# cc2652p2-tcp.net
KiCad netlist of a schematic drawn in EAGLE
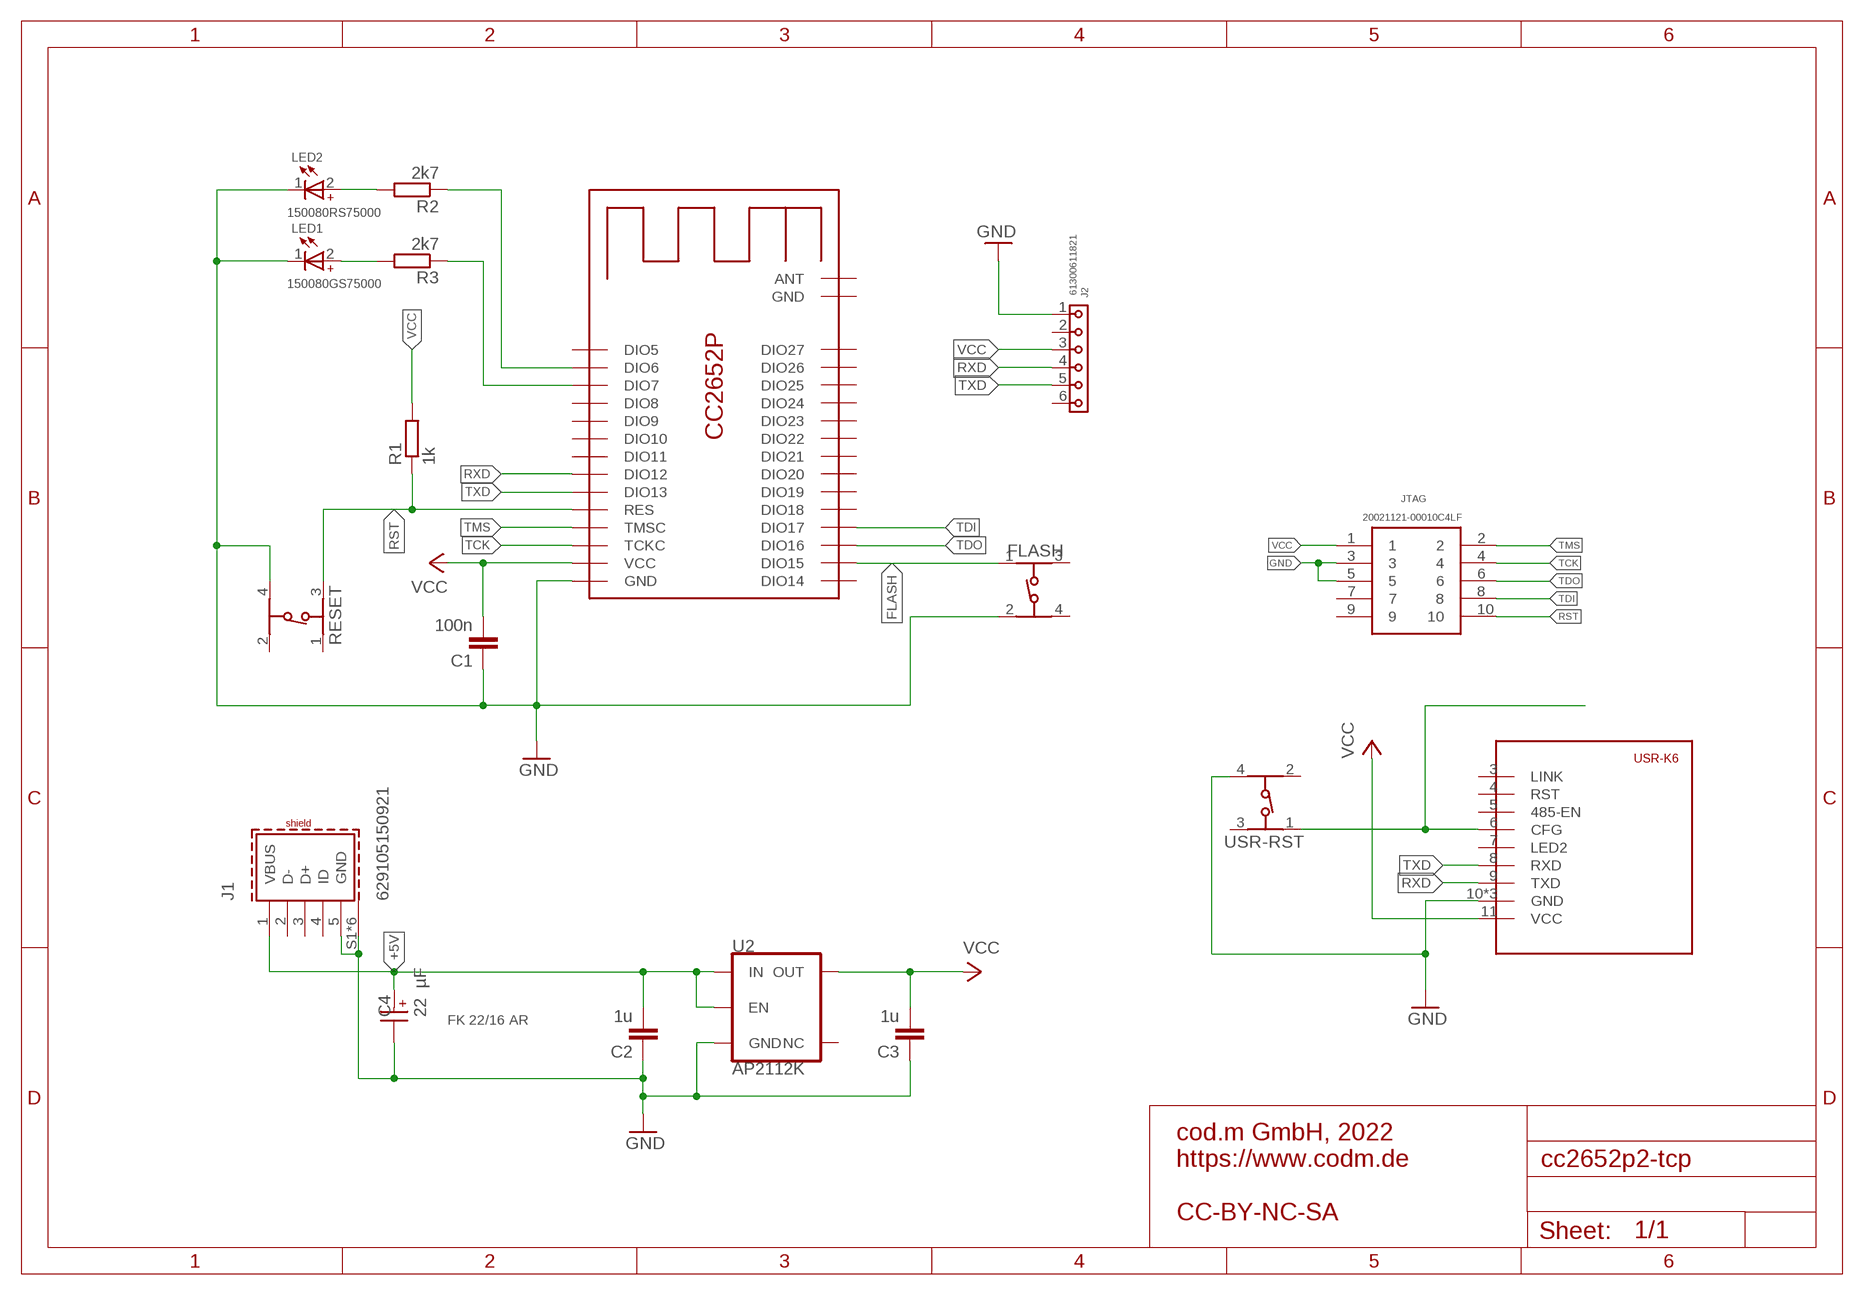
[diagram p0: schematic, sheet 1]

(export (version "E")
  (design (tool "Eeschema 10.0.6"))
  (components
    (comp (ref "C1")
      (value "100n")
      (footprint "eagle-import:C0805")
      (libsource (lib "eagle-import") (part "C-EUC0805"))
    )
    (comp (ref "C2")
      (value "1u")
      (footprint "eagle-import:C0805")
      (libsource (lib "eagle-import") (part "C-EUC0805"))
    )
    (comp (ref "C3")
      (value "1u")
      (footprint "eagle-import:C0805")
      (libsource (lib "eagle-import") (part "C-EUC0805"))
    )
    (comp (ref "C4")
      (value "22 µF")
      (footprint "eagle-import:WCAP-ASLL_5X5.5(DXL)")
      (libsource (lib "eagle-import") (part "WCAP-ASLL_5X5.5_865060342002"))
    )
    (comp (ref "FLASH")
      (value "434153017835")
      (footprint "eagle-import:434153017835")
      (libsource (lib "eagle-import") (part "434153017835"))
    )
    (comp (ref "J1")
      (value "629105150921")
      (footprint "eagle-import:629105150921")
      (libsource (lib "eagle-import") (part "629105150921"))
    )
    (comp (ref "J2")
      (value "61300611821")
      (footprint "eagle-import:61300611821")
      (libsource (lib "eagle-import") (part "6130XX11821_61300611821"))
    )
    (comp (ref "JTAG")
      (value "20021121-00010C4LF")
      (footprint "eagle-import:2002112100010C4LF")
      (fields (field (name "MOUSER_PART_NUMBER") "649-202112100010C4LF"))
      (libsource (lib "eagle-import") (part "20021121-00010C4LF"))
    )
    (comp (ref "LED1")
      (value "150080GS75000")
      (footprint "eagle-import:WL-SMCW_0805")
      (libsource (lib "eagle-import") (part "WL-SMCW_0805_150080GS75000"))
    )
    (comp (ref "LED2")
      (value "150080RS75000")
      (footprint "eagle-import:WL-SMCW_0805")
      (libsource (lib "eagle-import") (part "WL-SMCW_0805_150080RS75000"))
    )
    (comp (ref "R1")
      (value "1k")
      (footprint "eagle-import:R0805")
      (libsource (lib "eagle-import") (part "R-EU_R0805"))
    )
    (comp (ref "R2")
      (value "2k7")
      (footprint "eagle-import:R0805")
      (libsource (lib "eagle-import") (part "R-EU_R0805"))
    )
    (comp (ref "R3")
      (value "2k7")
      (footprint "eagle-import:R0805")
      (libsource (lib "eagle-import") (part "R-EU_R0805"))
    )
    (comp (ref "RESET")
      (value "434153017835")
      (footprint "eagle-import:434153017835")
      (libsource (lib "eagle-import") (part "434153017835"))
    )
    (comp (ref "U1")
      (value "CC2652P2-DUOWEISI")
      (footprint "eagle-import:CC2652P2-DUOWEISI")
      (libsource (lib "eagle-import") (part "CC2652P2-DUOWEISI"))
    )
    (comp (ref "U2")
      (value "AP2112K")
      (footprint "eagle-import:SOT23-5")
      (libsource (lib "eagle-import") (part "V_REG_AP2112K-3.3V"))
    )
    (comp (ref "U3")
      (value "USR-K6")
      (footprint "eagle-import:USR-K6")
      (libsource (lib "eagle-import") (part "USR-K6"))
    )
    (comp (ref "USR-RST")
      (value "434153017835")
      (footprint "eagle-import:434153017835")
      (libsource (lib "eagle-import") (part "434153017835"))
    )
  )
  (nets
    (net (code "1") (name "+5V") (class "Default")
      (node (ref "C2") (pin "2") (pinfunction "2_2") (pintype "passive"))
      (node (ref "C4") (pin "1") (pinfunction "+_1") (pintype "passive"))
      (node (ref "J1") (pin "1") (pinfunction "VBUS_1") (pintype "passive"))
      (node (ref "U2") (pin "1") (pinfunction "IN_1") (pintype "input"))
      (node (ref "U2") (pin "3") (pinfunction "EN_3") (pintype "input"))
    )
    (net (code "2") (name "FLASH") (class "Default")
      (node (ref "FLASH") (pin "1") (pinfunction "1_1") (pintype "passive"))
      (node (ref "U1") (pin "DIO15") (pinfunction "DIO15_DIO15") (pintype "bidirectional"))
    )
    (net (code "3") (name "GND") (class "Default")
      (node (ref "C1") (pin "1") (pinfunction "1_1") (pintype "passive"))
      (node (ref "C2") (pin "1") (pinfunction "1_1") (pintype "passive"))
      (node (ref "C3") (pin "1") (pinfunction "1_1") (pintype "passive"))
      (node (ref "C4") (pin "2") (pinfunction "-_2") (pintype "passive"))
      (node (ref "FLASH") (pin "2") (pinfunction "3_2") (pintype "passive"))
      (node (ref "J1") (pin "5") (pinfunction "GND_5") (pintype "passive"))
      (node (ref "J1") (pin "S1") (pinfunction "SHIELD_S1") (pintype "passive"))
      (node (ref "J1") (pin "S2") (pinfunction "SHIELD_S2") (pintype "passive"))
      (node (ref "J1") (pin "S3") (pinfunction "SHIELD_S3") (pintype "passive"))
      (node (ref "J1") (pin "S4") (pinfunction "SHIELD_S4") (pintype "passive"))
      (node (ref "J1") (pin "S5") (pinfunction "SHIELD_S5") (pintype "passive"))
      (node (ref "J1") (pin "S6") (pinfunction "SHIELD_S6") (pintype "passive"))
      (node (ref "J2") (pin "1") (pinfunction "1_1") (pintype "passive"))
      (node (ref "JTAG") (pin "3") (pinfunction "3_3") (pintype "bidirectional"))
      (node (ref "JTAG") (pin "5") (pinfunction "5_5") (pintype "bidirectional"))
      (node (ref "LED1") (pin "1") (pinfunction "-_1") (pintype "passive"))
      (node (ref "LED2") (pin "1") (pinfunction "-_1") (pintype "passive"))
      (node (ref "RESET") (pin "4") (pinfunction "4_4") (pintype "passive"))
      (node (ref "U1") (pin "GND") (pinfunction "GND_GND") (pintype "bidirectional"))
      (node (ref "U2") (pin "2") (pinfunction "GND_2") (pintype "input"))
      (node (ref "U3") (pin "10") (pinfunction "GND_10") (pintype "bidirectional"))
      (node (ref "U3") (pin "GND@1") (pinfunction "GND_GND@1") (pintype "bidirectional"))
      (node (ref "U3") (pin "GND@2") (pinfunction "GND_GND@2") (pintype "bidirectional"))
      (node (ref "USR-RST") (pin "4") (pinfunction "4_4") (pintype "passive"))
    )
    (net (code "4") (name "Net-(LED1-+)") (class "Default")
      (node (ref "LED1") (pin "2") (pinfunction "+_2") (pintype "passive"))
      (node (ref "R3") (pin "2") (pinfunction "2_2") (pintype "passive"))
    )
    (net (code "5") (name "Net-(LED2-+)") (class "Default")
      (node (ref "LED2") (pin "2") (pinfunction "+_2") (pintype "passive"))
      (node (ref "R2") (pin "2") (pinfunction "2_2") (pintype "passive"))
    )
    (net (code "6") (name "Net-(R2-Pad1)") (class "Default")
      (node (ref "R2") (pin "1") (pinfunction "1_1") (pintype "passive"))
      (node (ref "U1") (pin "DIO6") (pinfunction "DIO6_DIO6") (pintype "bidirectional"))
    )
    (net (code "7") (name "Net-(R3-Pad1)") (class "Default")
      (node (ref "R3") (pin "1") (pinfunction "1_1") (pintype "passive"))
      (node (ref "U1") (pin "DIO7") (pinfunction "DIO7_DIO7") (pintype "bidirectional"))
    )
    (net (code "8") (name "Net-(U3-CFG)") (class "Default")
      (node (ref "U3") (pin "6") (pinfunction "CFG_6") (pintype "bidirectional"))
      (node (ref "USR-RST") (pin "1") (pinfunction "1_1") (pintype "passive"))
    )
    (net (code "9") (name "RST") (class "Default")
      (node (ref "JTAG") (pin "10") (pinfunction "10_10") (pintype "bidirectional"))
      (node (ref "R1") (pin "1") (pinfunction "1_1") (pintype "passive"))
      (node (ref "RESET") (pin "3") (pinfunction "2_3") (pintype "passive"))
      (node (ref "U1") (pin "RES") (pinfunction "RES_RES") (pintype "bidirectional"))
    )
    (net (code "10") (name "RXD") (class "Default")
      (node (ref "J2") (pin "4") (pinfunction "4_4") (pintype "passive"))
      (node (ref "U1") (pin "DIO12") (pinfunction "DIO12_DIO12") (pintype "bidirectional"))
      (node (ref "U3") (pin "9") (pinfunction "TXD_9") (pintype "bidirectional"))
    )
    (net (code "11") (name "TCK") (class "Default")
      (node (ref "JTAG") (pin "4") (pinfunction "4_4") (pintype "bidirectional"))
      (node (ref "U1") (pin "TCKC") (pinfunction "TCKC_TCKC") (pintype "bidirectional"))
    )
    (net (code "12") (name "TDI") (class "Default")
      (node (ref "JTAG") (pin "8") (pinfunction "8_8") (pintype "bidirectional"))
      (node (ref "U1") (pin "DIO17") (pinfunction "DIO17_DIO17") (pintype "bidirectional"))
    )
    (net (code "13") (name "TDO") (class "Default")
      (node (ref "JTAG") (pin "6") (pinfunction "6_6") (pintype "bidirectional"))
      (node (ref "U1") (pin "DIO16") (pinfunction "DIO16_DIO16") (pintype "bidirectional"))
    )
    (net (code "14") (name "TMS") (class "Default")
      (node (ref "JTAG") (pin "2") (pinfunction "2_2") (pintype "bidirectional"))
      (node (ref "U1") (pin "TMSC") (pinfunction "TMSC_TMSC") (pintype "bidirectional"))
    )
    (net (code "15") (name "TXD") (class "Default")
      (node (ref "J2") (pin "5") (pinfunction "5_5") (pintype "passive"))
      (node (ref "U1") (pin "DIO13") (pinfunction "DIO13_DIO13") (pintype "bidirectional"))
      (node (ref "U3") (pin "8") (pinfunction "RXD_8") (pintype "bidirectional"))
    )
    (net (code "16") (name "VCC") (class "Default")
      (node (ref "C1") (pin "2") (pinfunction "2_2") (pintype "passive"))
      (node (ref "C3") (pin "2") (pinfunction "2_2") (pintype "passive"))
      (node (ref "J2") (pin "3") (pinfunction "3_3") (pintype "passive"))
      (node (ref "JTAG") (pin "1") (pinfunction "1_1") (pintype "bidirectional"))
      (node (ref "R1") (pin "2") (pinfunction "2_2") (pintype "passive"))
      (node (ref "U1") (pin "VCC") (pinfunction "VCC_VCC") (pintype "bidirectional"))
      (node (ref "U2") (pin "5") (pinfunction "OUT_5") (pintype "passive"))
      (node (ref "U3") (pin "11") (pinfunction "VCC_11") (pintype "bidirectional"))
    )
    (net (code "17") (name "unconnected-(FLASH-2-Pad3)") (class "Default")
      (node (ref "FLASH") (pin "3") (pinfunction "2_3") (pintype "passive"))
    )
    (net (code "18") (name "unconnected-(FLASH-Pad4)") (class "Default")
      (node (ref "FLASH") (pin "4") (pinfunction "4_4") (pintype "passive"))
    )
    (net (code "19") (name "unconnected-(J1-D+-Pad3)") (class "Default")
      (node (ref "J1") (pin "3") (pinfunction "D+_3") (pintype "passive"))
    )
    (net (code "20") (name "unconnected-(J1-D--Pad2)") (class "Default")
      (node (ref "J1") (pin "2") (pinfunction "D-_2") (pintype "passive"))
    )
    (net (code "21") (name "unconnected-(J1-ID-Pad4)") (class "Default")
      (node (ref "J1") (pin "4") (pinfunction "ID_4") (pintype "passive"))
    )
    (net (code "22") (name "unconnected-(J2-Pad2)") (class "Default")
      (node (ref "J2") (pin "2") (pinfunction "2_2") (pintype "passive"))
    )
    (net (code "23") (name "unconnected-(J2-Pad6)") (class "Default")
      (node (ref "J2") (pin "6") (pinfunction "6_6") (pintype "passive"))
    )
    (net (code "24") (name "unconnected-(JTAG-Pad7)") (class "Default")
      (node (ref "JTAG") (pin "7") (pinfunction "7_7") (pintype "bidirectional"))
    )
    (net (code "25") (name "unconnected-(JTAG-Pad9)") (class "Default")
      (node (ref "JTAG") (pin "9") (pinfunction "9_9") (pintype "bidirectional"))
    )
    (net (code "26") (name "unconnected-(RESET-3-Pad2)") (class "Default")
      (node (ref "RESET") (pin "2") (pinfunction "3_2") (pintype "passive"))
    )
    (net (code "27") (name "unconnected-(RESET-Pad1)") (class "Default")
      (node (ref "RESET") (pin "1") (pinfunction "1_1") (pintype "passive"))
    )
    (net (code "28") (name "unconnected-(U1-GND-PadGND@1)") (class "Default")
      (node (ref "U1") (pin "GND@1") (pinfunction "GND_GND@1") (pintype "bidirectional"))
    )
    (net (code "29") (name "unconnected-(U1-PadANT)") (class "Default")
      (node (ref "U1") (pin "ANT") (pinfunction "ANT_ANT") (pintype "bidirectional"))
    )
    (net (code "30") (name "unconnected-(U1-PadDIO5)") (class "Default")
      (node (ref "U1") (pin "DIO5") (pinfunction "DIO5_DIO5") (pintype "bidirectional"))
    )
    (net (code "31") (name "unconnected-(U1-PadDIO8)") (class "Default")
      (node (ref "U1") (pin "DIO8") (pinfunction "DIO8_DIO8") (pintype "bidirectional"))
    )
    (net (code "32") (name "unconnected-(U1-PadDIO9)") (class "Default")
      (node (ref "U1") (pin "DIO9") (pinfunction "DIO9_DIO9") (pintype "bidirectional"))
    )
    (net (code "33") (name "unconnected-(U1-PadDIO10)") (class "Default")
      (node (ref "U1") (pin "DIO10") (pinfunction "DIO10_DIO10") (pintype "bidirectional"))
    )
    (net (code "34") (name "unconnected-(U1-PadDIO11)") (class "Default")
      (node (ref "U1") (pin "DIO11") (pinfunction "DIO11_DIO11") (pintype "bidirectional"))
    )
    (net (code "35") (name "unconnected-(U1-PadDIO14)") (class "Default")
      (node (ref "U1") (pin "DIO14") (pinfunction "DIO14_DIO14") (pintype "bidirectional"))
    )
    (net (code "36") (name "unconnected-(U1-PadDIO18)") (class "Default")
      (node (ref "U1") (pin "DIO18") (pinfunction "DIO18_DIO18") (pintype "bidirectional"))
    )
    (net (code "37") (name "unconnected-(U1-PadDIO19)") (class "Default")
      (node (ref "U1") (pin "DIO19") (pinfunction "DIO19_DIO19") (pintype "bidirectional"))
    )
    (net (code "38") (name "unconnected-(U1-PadDIO20)") (class "Default")
      (node (ref "U1") (pin "DIO20") (pinfunction "DIO20_DIO20") (pintype "bidirectional"))
    )
    (net (code "39") (name "unconnected-(U1-PadDIO21)") (class "Default")
      (node (ref "U1") (pin "DIO21") (pinfunction "DIO21_DIO21") (pintype "bidirectional"))
    )
    (net (code "40") (name "unconnected-(U1-PadDIO22)") (class "Default")
      (node (ref "U1") (pin "DIO22") (pinfunction "DIO22_DIO22") (pintype "bidirectional"))
    )
    (net (code "41") (name "unconnected-(U1-PadDIO23)") (class "Default")
      (node (ref "U1") (pin "DIO23") (pinfunction "DIO23_DIO23") (pintype "bidirectional"))
    )
    (net (code "42") (name "unconnected-(U1-PadDIO24)") (class "Default")
      (node (ref "U1") (pin "DIO24") (pinfunction "DIO24_DIO24") (pintype "bidirectional"))
    )
    (net (code "43") (name "unconnected-(U1-PadDIO25)") (class "Default")
      (node (ref "U1") (pin "DIO25") (pinfunction "DIO25_DIO25") (pintype "bidirectional"))
    )
    (net (code "44") (name "unconnected-(U1-PadDIO26)") (class "Default")
      (node (ref "U1") (pin "DIO26") (pinfunction "DIO26_DIO26") (pintype "bidirectional"))
    )
    (net (code "45") (name "unconnected-(U1-PadDIO27)") (class "Default")
      (node (ref "U1") (pin "DIO27") (pinfunction "DIO27_DIO27") (pintype "bidirectional"))
    )
    (net (code "46") (name "unconnected-(U2-NC-Pad4)") (class "Default")
      (node (ref "U2") (pin "4") (pinfunction "NC_4") (pintype "no_connect"))
    )
    (net (code "47") (name "unconnected-(U3-485-EN-Pad5)") (class "Default")
      (node (ref "U3") (pin "5") (pinfunction "485-EN_5") (pintype "bidirectional"))
    )
    (net (code "48") (name "unconnected-(U3-LED2-Pad7)") (class "Default")
      (node (ref "U3") (pin "7") (pinfunction "LED2_7") (pintype "bidirectional"))
    )
    (net (code "49") (name "unconnected-(U3-LINK-Pad3)") (class "Default")
      (node (ref "U3") (pin "3") (pinfunction "LINK_3") (pintype "bidirectional"))
    )
    (net (code "50") (name "unconnected-(U3-RST-Pad4)") (class "Default")
      (node (ref "U3") (pin "4") (pinfunction "RST_4") (pintype "bidirectional"))
    )
    (net (code "51") (name "unconnected-(USR-RST-2-Pad3)") (class "Default")
      (node (ref "USR-RST") (pin "3") (pinfunction "2_3") (pintype "passive"))
    )
    (net (code "52") (name "unconnected-(USR-RST-3-Pad2)") (class "Default")
      (node (ref "USR-RST") (pin "2") (pinfunction "3_2") (pintype "passive"))
    )
  )
)
